# xmas_tree_proto_v2.net
KiCad netlist of a schematic drawn in EAGLE
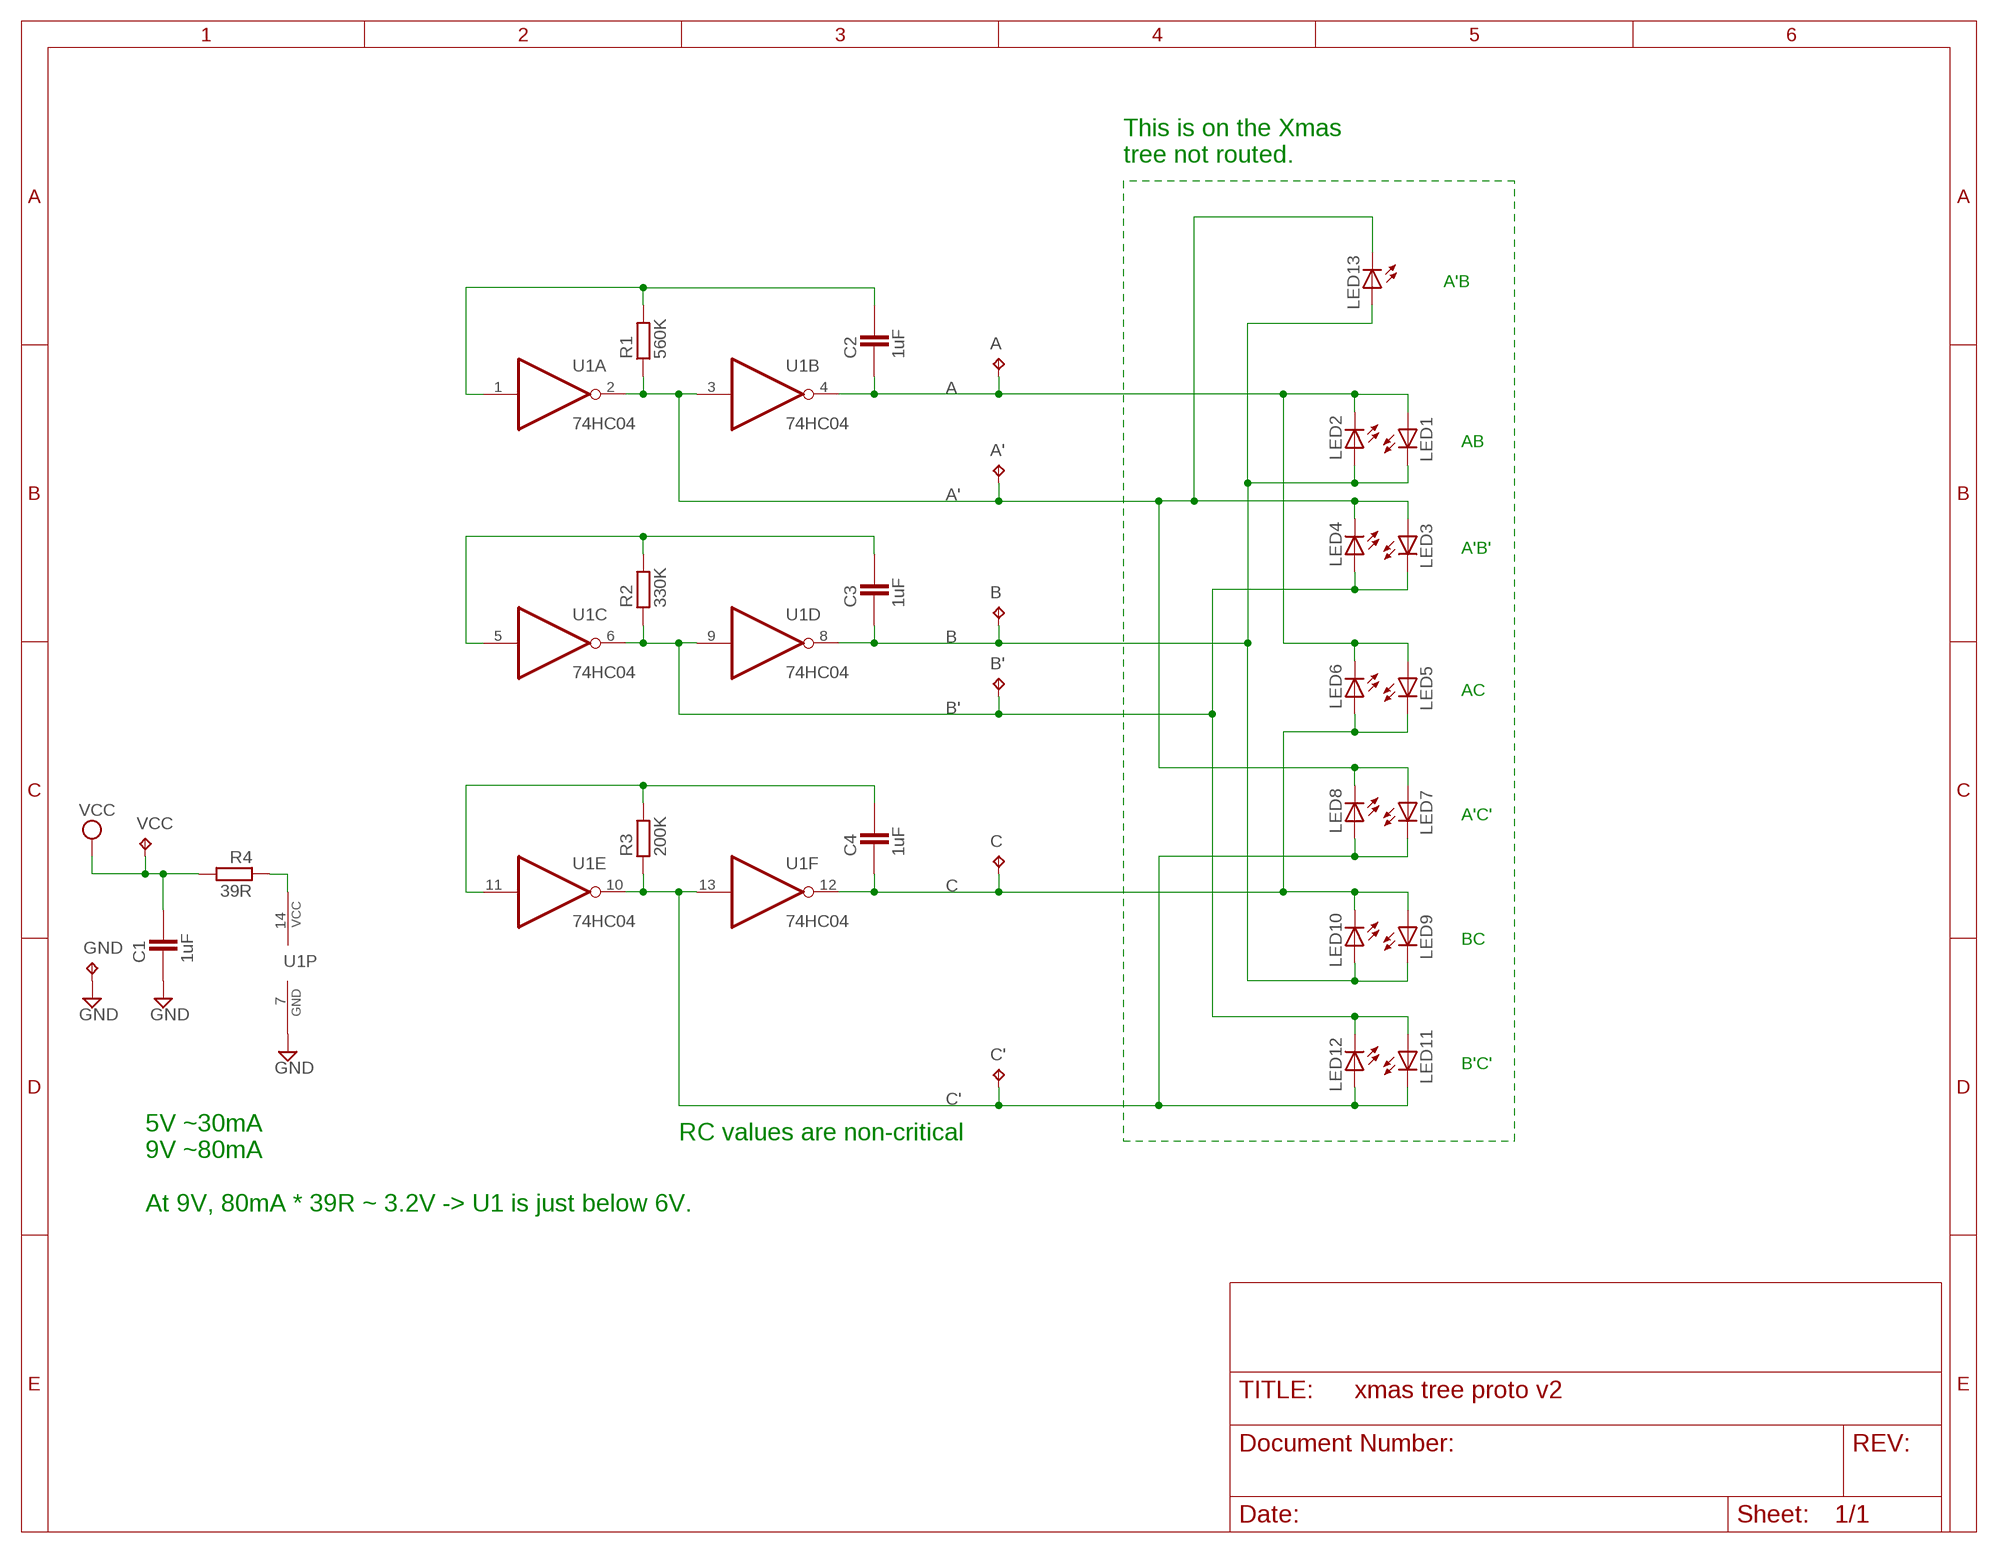
[diagram p0: schematic, sheet 1]

(export (version "E")
  (design (tool "Eeschema 10.0.6"))
  (components
    (comp (ref "A")
      (value "TPTP10SQ")
      (footprint "eagle-import:TP10SQ")
      (libsource (lib "eagle-import") (part "TPTP10SQ"))
    )
    (comp (ref "A'")
      (value "TPTP10SQ")
      (footprint "eagle-import:TP10SQ")
      (libsource (lib "eagle-import") (part "TPTP10SQ"))
    )
    (comp (ref "B")
      (value "TPTP10SQ")
      (footprint "eagle-import:TP10SQ")
      (libsource (lib "eagle-import") (part "TPTP10SQ"))
    )
    (comp (ref "B'")
      (value "TPTP10SQ")
      (footprint "eagle-import:TP10SQ")
      (libsource (lib "eagle-import") (part "TPTP10SQ"))
    )
    (comp (ref "C")
      (value "TPTP10SQ")
      (footprint "eagle-import:TP10SQ")
      (libsource (lib "eagle-import") (part "TPTP10SQ"))
    )
    (comp (ref "C'")
      (value "TPTP10SQ")
      (footprint "eagle-import:TP10SQ")
      (libsource (lib "eagle-import") (part "TPTP10SQ"))
    )
    (comp (ref "C1")
      (value "1uF")
      (footprint "eagle-import:CAP2012X70N")
      (libsource (lib "eagle-import") (part "CAPACITOR_0805N"))
    )
    (comp (ref "C2")
      (value "1uF")
      (footprint "eagle-import:CAPC1608X92N")
      (libsource (lib "eagle-import") (part "CAPACITOR_0603"))
    )
    (comp (ref "C3")
      (value "1uF")
      (footprint "eagle-import:CAPC1608X92N")
      (libsource (lib "eagle-import") (part "CAPACITOR_0603"))
    )
    (comp (ref "C4")
      (value "1uF")
      (footprint "eagle-import:CAPC1608X92N")
      (libsource (lib "eagle-import") (part "CAPACITOR_0603"))
    )
    (comp (ref "GND")
      (value "TPTP20SQ")
      (footprint "eagle-import:TP20SQ")
      (libsource (lib "eagle-import") (part "TPTP20SQ"))
    )
    (comp (ref "LED1")
      (value "LED3MM")
      (footprint "eagle-import:LED3MM")
      (libsource (lib "eagle-import") (part "LED3MM"))
    )
    (comp (ref "LED2")
      (value "LED3MM")
      (footprint "eagle-import:LED3MM")
      (libsource (lib "eagle-import") (part "LED3MM"))
    )
    (comp (ref "LED3")
      (value "LED3MM")
      (footprint "eagle-import:LED3MM")
      (libsource (lib "eagle-import") (part "LED3MM"))
    )
    (comp (ref "LED4")
      (value "LED3MM")
      (footprint "eagle-import:LED3MM")
      (libsource (lib "eagle-import") (part "LED3MM"))
    )
    (comp (ref "LED5")
      (value "LED3MM")
      (footprint "eagle-import:LED3MM")
      (libsource (lib "eagle-import") (part "LED3MM"))
    )
    (comp (ref "LED6")
      (value "LED3MM")
      (footprint "eagle-import:LED3MM")
      (libsource (lib "eagle-import") (part "LED3MM"))
    )
    (comp (ref "LED7")
      (value "LED3MM")
      (footprint "eagle-import:LED3MM")
      (libsource (lib "eagle-import") (part "LED3MM"))
    )
    (comp (ref "LED8")
      (value "LED3MM")
      (footprint "eagle-import:LED3MM")
      (libsource (lib "eagle-import") (part "LED3MM"))
    )
    (comp (ref "LED9")
      (value "LED3MM")
      (footprint "eagle-import:LED3MM")
      (libsource (lib "eagle-import") (part "LED3MM"))
    )
    (comp (ref "LED10")
      (value "LED3MM")
      (footprint "eagle-import:LED3MM")
      (libsource (lib "eagle-import") (part "LED3MM"))
    )
    (comp (ref "LED11")
      (value "LED3MM")
      (footprint "eagle-import:LED3MM")
      (libsource (lib "eagle-import") (part "LED3MM"))
    )
    (comp (ref "LED12")
      (value "LED3MM")
      (footprint "eagle-import:LED3MM")
      (libsource (lib "eagle-import") (part "LED3MM"))
    )
    (comp (ref "LED13")
      (value "LED3MM")
      (footprint "eagle-import:LED3MM")
      (libsource (lib "eagle-import") (part "LED3MM"))
    )
    (comp (ref "R1")
      (value "560K")
      (footprint "eagle-import:RESC1608X55N")
      (libsource (lib "eagle-import") (part "RESISTOR_0603"))
    )
    (comp (ref "R2")
      (value "330K")
      (footprint "eagle-import:RESC1608X55N")
      (libsource (lib "eagle-import") (part "RESISTOR_0603"))
    )
    (comp (ref "R3")
      (value "200K")
      (footprint "eagle-import:RESC1608X55N")
      (libsource (lib "eagle-import") (part "RESISTOR_0603"))
    )
    (comp (ref "R4")
      (value "39R")
      (footprint "eagle-import:RESC1608X55N")
      (libsource (lib "eagle-import") (part "RESISTOR_0603"))
    )
    (comp (ref "U1")
      (value "74HC04")
      (footprint "eagle-import:SO14")
      (libsource (lib "eagle-import") (part "7404DAS"))
    )
    (comp (ref "VCC")
      (value "TPTP20SQ")
      (footprint "eagle-import:TP20SQ")
      (libsource (lib "eagle-import") (part "TPTP20SQ"))
    )
  )
  (nets
    (net (code "1") (name "/A") (class "Default")
      (node (ref "A") (pin "TP") (pinfunction "TP_TP") (pintype "input"))
      (node (ref "C2") (pin "1") (pinfunction "1_1") (pintype "passive"))
      (node (ref "LED1") (pin "A") (pinfunction "A_A") (pintype "passive"))
      (node (ref "LED2") (pin "K") (pinfunction "C_K") (pintype "passive"))
      (node (ref "LED5") (pin "A") (pinfunction "A_A") (pintype "passive"))
      (node (ref "LED6") (pin "K") (pinfunction "C_K") (pintype "passive"))
      (node (ref "U1") (pin "4") (pinfunction "O_4") (pintype "output"))
    )
    (net (code "2") (name "/A'") (class "Default")
      (node (ref "A'") (pin "TP") (pinfunction "TP_TP") (pintype "input"))
      (node (ref "LED13") (pin "K") (pinfunction "C_K") (pintype "passive"))
      (node (ref "LED3") (pin "A") (pinfunction "A_A") (pintype "passive"))
      (node (ref "LED4") (pin "K") (pinfunction "C_K") (pintype "passive"))
      (node (ref "LED7") (pin "A") (pinfunction "A_A") (pintype "passive"))
      (node (ref "LED8") (pin "K") (pinfunction "C_K") (pintype "passive"))
      (node (ref "R1") (pin "1") (pinfunction "1_1") (pintype "passive"))
      (node (ref "U1") (pin "2") (pinfunction "O_2") (pintype "output"))
      (node (ref "U1") (pin "3") (pinfunction "I_3") (pintype "input"))
    )
    (net (code "3") (name "/B") (class "Default")
      (node (ref "B") (pin "TP") (pinfunction "TP_TP") (pintype "input"))
      (node (ref "C3") (pin "1") (pinfunction "1_1") (pintype "passive"))
      (node (ref "LED1") (pin "K") (pinfunction "C_K") (pintype "passive"))
      (node (ref "LED10") (pin "A") (pinfunction "A_A") (pintype "passive"))
      (node (ref "LED13") (pin "A") (pinfunction "A_A") (pintype "passive"))
      (node (ref "LED2") (pin "A") (pinfunction "A_A") (pintype "passive"))
      (node (ref "LED9") (pin "K") (pinfunction "C_K") (pintype "passive"))
      (node (ref "U1") (pin "8") (pinfunction "O_8") (pintype "output"))
    )
    (net (code "4") (name "/B'") (class "Default")
      (node (ref "B'") (pin "TP") (pinfunction "TP_TP") (pintype "input"))
      (node (ref "LED11") (pin "A") (pinfunction "A_A") (pintype "passive"))
      (node (ref "LED12") (pin "K") (pinfunction "C_K") (pintype "passive"))
      (node (ref "LED3") (pin "K") (pinfunction "C_K") (pintype "passive"))
      (node (ref "LED4") (pin "A") (pinfunction "A_A") (pintype "passive"))
      (node (ref "R2") (pin "1") (pinfunction "1_1") (pintype "passive"))
      (node (ref "U1") (pin "6") (pinfunction "O_6") (pintype "output"))
      (node (ref "U1") (pin "9") (pinfunction "I_9") (pintype "input"))
    )
    (net (code "5") (name "/C") (class "Default")
      (node (ref "C") (pin "TP") (pinfunction "TP_TP") (pintype "input"))
      (node (ref "C4") (pin "1") (pinfunction "1_1") (pintype "passive"))
      (node (ref "LED10") (pin "K") (pinfunction "C_K") (pintype "passive"))
      (node (ref "LED5") (pin "K") (pinfunction "C_K") (pintype "passive"))
      (node (ref "LED6") (pin "A") (pinfunction "A_A") (pintype "passive"))
      (node (ref "LED9") (pin "A") (pinfunction "A_A") (pintype "passive"))
      (node (ref "U1") (pin "12") (pinfunction "O_12") (pintype "output"))
    )
    (net (code "6") (name "/C'") (class "Default")
      (node (ref "C'") (pin "TP") (pinfunction "TP_TP") (pintype "input"))
      (node (ref "LED11") (pin "K") (pinfunction "C_K") (pintype "passive"))
      (node (ref "LED12") (pin "A") (pinfunction "A_A") (pintype "passive"))
      (node (ref "LED7") (pin "K") (pinfunction "C_K") (pintype "passive"))
      (node (ref "LED8") (pin "A") (pinfunction "A_A") (pintype "passive"))
      (node (ref "R3") (pin "1") (pinfunction "1_1") (pintype "passive"))
      (node (ref "U1") (pin "10") (pinfunction "O_10") (pintype "output"))
      (node (ref "U1") (pin "13") (pinfunction "I_13") (pintype "input"))
    )
    (net (code "7") (name "GND") (class "Default")
      (node (ref "C1") (pin "1") (pinfunction "1_1") (pintype "passive"))
      (node (ref "GND") (pin "TP") (pinfunction "TP_TP") (pintype "input"))
      (node (ref "U1") (pin "7") (pinfunction "GND_7") (pintype "power_in"))
    )
    (net (code "8") (name "Net-(U1A-I)") (class "Default")
      (node (ref "C2") (pin "2") (pinfunction "2_2") (pintype "passive"))
      (node (ref "R1") (pin "2") (pinfunction "2_2") (pintype "passive"))
      (node (ref "U1") (pin "1") (pinfunction "I_1") (pintype "input"))
    )
    (net (code "9") (name "Net-(U1C-I)") (class "Default")
      (node (ref "C3") (pin "2") (pinfunction "2_2") (pintype "passive"))
      (node (ref "R2") (pin "2") (pinfunction "2_2") (pintype "passive"))
      (node (ref "U1") (pin "5") (pinfunction "I_5") (pintype "input"))
    )
    (net (code "10") (name "Net-(U1E-I)") (class "Default")
      (node (ref "C4") (pin "2") (pinfunction "2_2") (pintype "passive"))
      (node (ref "R3") (pin "2") (pinfunction "2_2") (pintype "passive"))
      (node (ref "U1") (pin "11") (pinfunction "I_11") (pintype "input"))
    )
    (net (code "11") (name "Net-(U1G-VCC)") (class "Default")
      (node (ref "R4") (pin "1") (pinfunction "1_1") (pintype "passive"))
      (node (ref "U1") (pin "14") (pinfunction "VCC_14") (pintype "power_in"))
    )
    (net (code "12") (name "VCC") (class "Default")
      (node (ref "C1") (pin "2") (pinfunction "2_2") (pintype "passive"))
      (node (ref "R4") (pin "2") (pinfunction "2_2") (pintype "passive"))
      (node (ref "VCC") (pin "TP") (pinfunction "TP_TP") (pintype "input"))
    )
  )
)
